# Connectors.net
KiCad netlist of a schematic drawn in Altium Designer
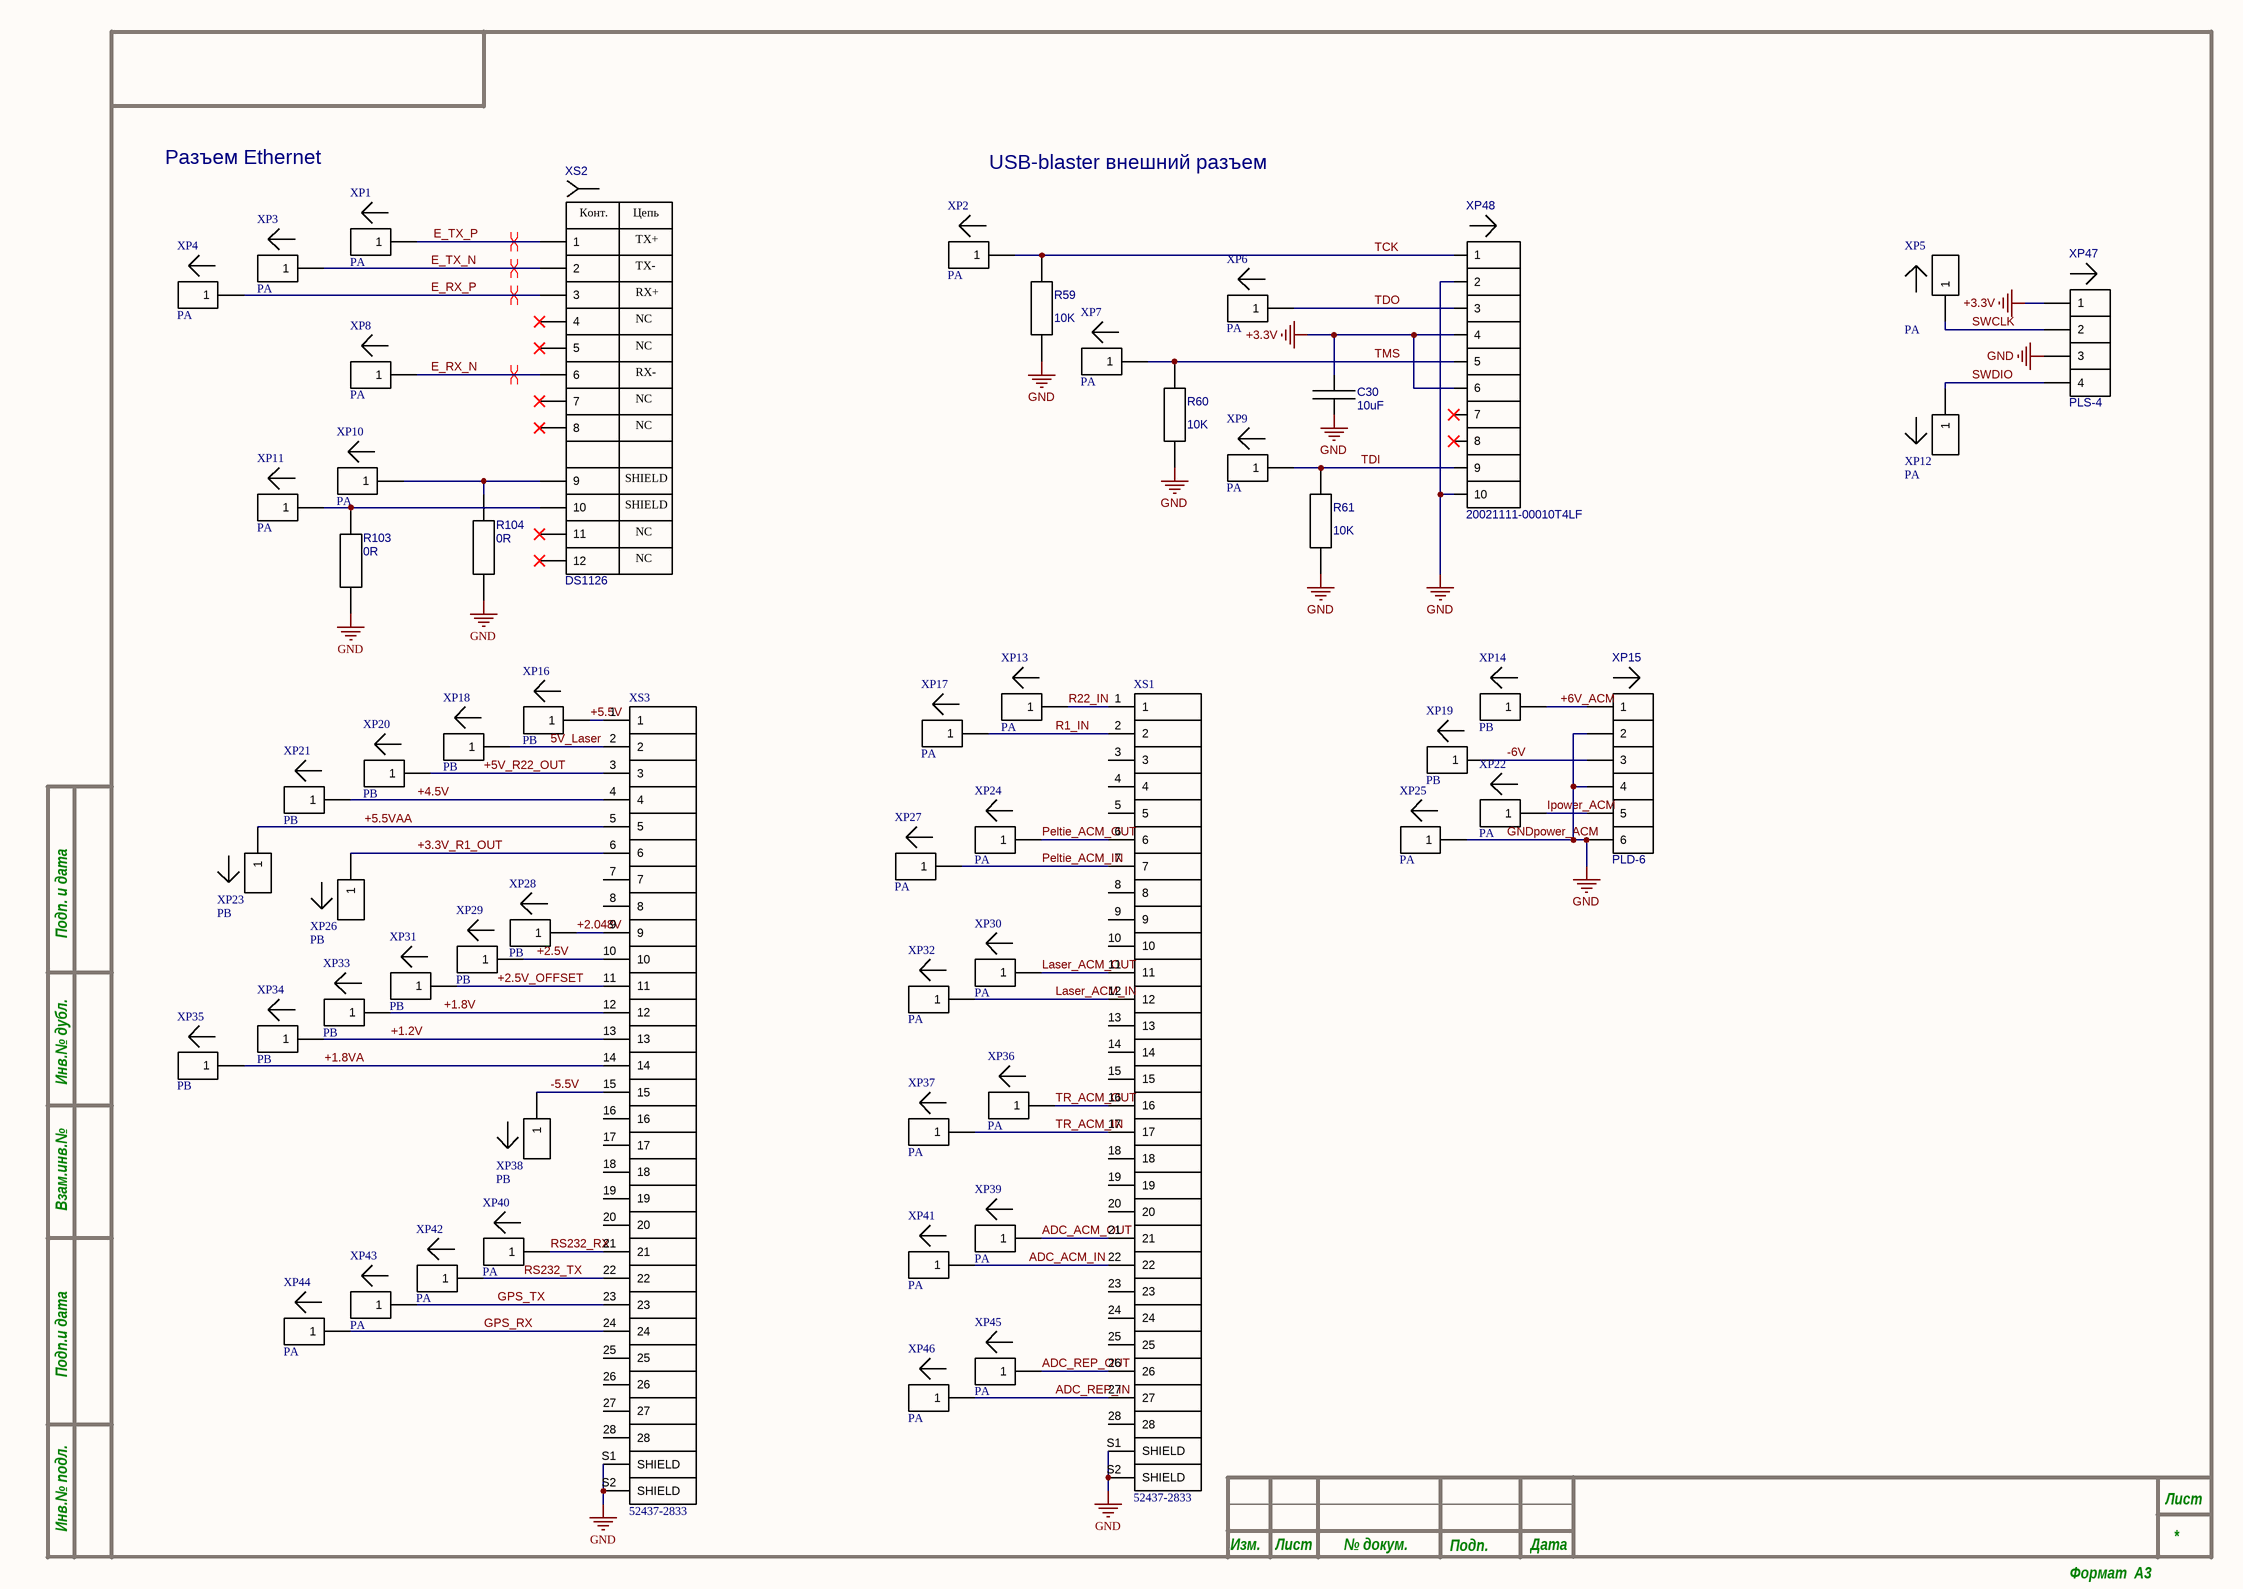
[diagram p0: Connectors — копия.SchDoc]

(export (version "E")
  (design (tool "Eeschema 10.0.6"))
  (components
    (comp (ref "C30")
      (value "10uF")
      (footprint "0402C")
      (description "C0402-10UF 10% 10V")
      (fields
        (field (name "PART NUMBER") "SMD CAP CER 10UF ±10% 10V X5R 0402")
        (field (name "ADDED_BY") "Rutel@Mail.ru")
      )
      (libsource (lib "Test_Stand_Pergam") (part "C0402-10UF 10% 10V"))
    )
    (comp (ref "R59")
      (value "10K")
      (footprint "R0402")
      (description "Resistor SMD 10K 1% 0402")
      (fields
        (field (name "PART NUMBER") "SMD RES 10 KOHM 1% ±100ppm/°C 0402")
        (field (name "ADDED_BY") "Rutel@teslatec.ru")
      )
      (libsource (lib "Test_Stand_Pergam") (part "R0402-10K"))
    )
    (comp (ref "R60")
      (value "10K")
      (footprint "R0402")
      (description "Resistor SMD 10K 1% 0402")
      (fields
        (field (name "PART NUMBER") "SMD RES 10 KOHM 1% ±100ppm/°C 0402")
        (field (name "ADDED_BY") "Rutel@teslatec.ru")
      )
      (libsource (lib "Test_Stand_Pergam") (part "R0402-10K"))
    )
    (comp (ref "R61")
      (value "10K")
      (footprint "R0402")
      (description "Resistor SMD 10K 1% 0402")
      (fields
        (field (name "PART NUMBER") "SMD RES 10 KOHM 1% ±100ppm/°C 0402")
        (field (name "ADDED_BY") "Rutel@teslatec.ru")
      )
      (libsource (lib "Test_Stand_Pergam") (part "R0402-10K"))
    )
    (comp (ref "R103")
      (value "0R")
      (footprint "R0402")
      (description "Resistor SMD 0R 1% 0402")
      (fields
        (field (name "PART NUMBER") "SMD RES 0R 0402")
        (field (name "ADDED_BY") "irdolgopolowa@yandex.ru")
      )
      (libsource (lib "Test_Stand_Pergam") (part "R0402-0R"))
    )
    (comp (ref "R104")
      (value "0R")
      (footprint "R0402")
      (description "Resistor SMD 0R 1% 0402")
      (fields
        (field (name "PART NUMBER") "SMD RES 0R 0402")
        (field (name "ADDED_BY") "irdolgopolowa@yandex.ru")
      )
      (libsource (lib "Test_Stand_Pergam") (part "R0402-0R"))
    )
    (comp (ref "XP1")
      (value "PA")
      (footprint "POGO PIN P100-A2/B1")
      (description "Pogo pin, 33.35x1.36")
      (fields
        (field (name "PART NUMBER") "P100-A2 / P100-A")
        (field (name "ADDED_BY") "irdolgopolowa@yandex.ru")
      )
      (libsource (lib "Test_Stand_Pergam") (part "P100-A2 / P100-A"))
    )
    (comp (ref "XP2")
      (value "PA")
      (footprint "POGO PIN P100-A2/B1")
      (description "Pogo pin, 33.35x1.36")
      (fields
        (field (name "PART NUMBER") "P100-A2 / P100-A")
        (field (name "ADDED_BY") "irdolgopolowa@yandex.ru")
      )
      (libsource (lib "Test_Stand_Pergam") (part "P100-A2 / P100-A"))
    )
    (comp (ref "XP3")
      (value "PA")
      (footprint "POGO PIN P100-A2/B1")
      (description "Pogo pin, 33.35x1.36")
      (fields
        (field (name "PART NUMBER") "P100-A2 / P100-A")
        (field (name "ADDED_BY") "irdolgopolowa@yandex.ru")
      )
      (libsource (lib "Test_Stand_Pergam") (part "P100-A2 / P100-A"))
    )
    (comp (ref "XP4")
      (value "PA")
      (footprint "POGO PIN P100-A2/B1")
      (description "Pogo pin, 33.35x1.36")
      (fields
        (field (name "PART NUMBER") "P100-A2 / P100-A")
        (field (name "ADDED_BY") "irdolgopolowa@yandex.ru")
      )
      (libsource (lib "Test_Stand_Pergam") (part "P100-A2 / P100-A"))
    )
    (comp (ref "XP5")
      (value "PA")
      (footprint "POGO PIN P100-A2/B1")
      (description "Pogo pin, 33.35x1.36")
      (fields
        (field (name "PART NUMBER") "P100-A2 / P100-A")
        (field (name "ADDED_BY") "irdolgopolowa@yandex.ru")
      )
      (libsource (lib "Test_Stand_Pergam") (part "P100-A2 / P100-A"))
    )
    (comp (ref "XP6")
      (value "PA")
      (footprint "POGO PIN P100-A2/B1")
      (description "Pogo pin, 33.35x1.36")
      (fields
        (field (name "PART NUMBER") "P100-A2 / P100-A")
        (field (name "ADDED_BY") "irdolgopolowa@yandex.ru")
      )
      (libsource (lib "Test_Stand_Pergam") (part "P100-A2 / P100-A"))
    )
    (comp (ref "XP7")
      (value "PA")
      (footprint "POGO PIN P100-A2/B1")
      (description "Pogo pin, 33.35x1.36")
      (fields
        (field (name "PART NUMBER") "P100-A2 / P100-A")
        (field (name "ADDED_BY") "irdolgopolowa@yandex.ru")
      )
      (libsource (lib "Test_Stand_Pergam") (part "P100-A2 / P100-A"))
    )
    (comp (ref "XP8")
      (value "PA")
      (footprint "POGO PIN P100-A2/B1")
      (description "Pogo pin, 33.35x1.36")
      (fields
        (field (name "PART NUMBER") "P100-A2 / P100-A")
        (field (name "ADDED_BY") "irdolgopolowa@yandex.ru")
      )
      (libsource (lib "Test_Stand_Pergam") (part "P100-A2 / P100-A"))
    )
    (comp (ref "XP9")
      (value "PA")
      (footprint "POGO PIN P100-A2/B1")
      (description "Pogo pin, 33.35x1.36")
      (fields
        (field (name "PART NUMBER") "P100-A2 / P100-A")
        (field (name "ADDED_BY") "irdolgopolowa@yandex.ru")
      )
      (libsource (lib "Test_Stand_Pergam") (part "P100-A2 / P100-A"))
    )
    (comp (ref "XP10")
      (value "PA")
      (footprint "POGO PIN P100-A2/B1")
      (description "Pogo pin, 33.35x1.36")
      (fields
        (field (name "PART NUMBER") "P100-A2 / P100-A")
        (field (name "ADDED_BY") "irdolgopolowa@yandex.ru")
      )
      (libsource (lib "Test_Stand_Pergam") (part "P100-A2 / P100-A"))
    )
    (comp (ref "XP11")
      (value "PA")
      (footprint "POGO PIN P100-A2/B1")
      (description "Pogo pin, 33.35x1.36")
      (fields
        (field (name "PART NUMBER") "P100-A2 / P100-A")
        (field (name "ADDED_BY") "irdolgopolowa@yandex.ru")
      )
      (libsource (lib "Test_Stand_Pergam") (part "P100-A2 / P100-A"))
    )
    (comp (ref "XP12")
      (value "PA")
      (footprint "POGO PIN P100-A2/B1")
      (description "Pogo pin, 33.35x1.36")
      (fields
        (field (name "PART NUMBER") "P100-A2 / P100-A")
        (field (name "ADDED_BY") "irdolgopolowa@yandex.ru")
      )
      (libsource (lib "Test_Stand_Pergam") (part "P100-A2 / P100-A"))
    )
    (comp (ref "XP13")
      (value "PA")
      (footprint "POGO PIN P100-A2/B1")
      (description "Pogo pin, 33.35x1.36")
      (fields
        (field (name "PART NUMBER") "P100-A2 / P100-A")
        (field (name "ADDED_BY") "irdolgopolowa@yandex.ru")
      )
      (libsource (lib "Test_Stand_Pergam") (part "P100-A2 / P100-A"))
    )
    (comp (ref "XP14")
      (value "PB")
      (footprint "POGO PIN P100-A2/B1")
      (description "Pogo pin, 33.35x1.36")
      (fields (field (name "PART NUMBER") "P100-B1") (field (name "ADDED_BY") "irdolgopolowa@yandex.ru"))
      (libsource (lib "Test_Stand_Pergam") (part "P100-B1"))
    )
    (comp (ref "XP15")
      (value "PLD-6")
      (footprint "PLD-6")
      (description "Pin Header Pitch 2.54mm")
      (fields
        (field (name "PART NUMBER") "PLD-6 (DS1021-2x3)")
        (field (name "ADDED_BY") "ponomarev_ke@teslatec.ru")
      )
      (libsource (lib "Test_Stand_Pergam") (part "PLD-6"))
    )
    (comp (ref "XP16")
      (value "PB")
      (footprint "POGO PIN P100-A2/B1")
      (description "Pogo pin, 33.35x1.36")
      (fields (field (name "PART NUMBER") "P100-B1") (field (name "ADDED_BY") "irdolgopolowa@yandex.ru"))
      (libsource (lib "Test_Stand_Pergam") (part "P100-B1"))
    )
    (comp (ref "XP17")
      (value "PA")
      (footprint "POGO PIN P100-A2/B1")
      (description "Pogo pin, 33.35x1.36")
      (fields
        (field (name "PART NUMBER") "P100-A2 / P100-A")
        (field (name "ADDED_BY") "irdolgopolowa@yandex.ru")
      )
      (libsource (lib "Test_Stand_Pergam") (part "P100-A2 / P100-A"))
    )
    (comp (ref "XP18")
      (value "PB")
      (footprint "POGO PIN P100-A2/B1")
      (description "Pogo pin, 33.35x1.36")
      (fields (field (name "PART NUMBER") "P100-B1") (field (name "ADDED_BY") "irdolgopolowa@yandex.ru"))
      (libsource (lib "Test_Stand_Pergam") (part "P100-B1"))
    )
    (comp (ref "XP19")
      (value "PB")
      (footprint "POGO PIN P100-A2/B1")
      (description "Pogo pin, 33.35x1.36")
      (fields (field (name "PART NUMBER") "P100-B1") (field (name "ADDED_BY") "irdolgopolowa@yandex.ru"))
      (libsource (lib "Test_Stand_Pergam") (part "P100-B1"))
    )
    (comp (ref "XP20")
      (value "PB")
      (footprint "POGO PIN P100-A2/B1")
      (description "Pogo pin, 33.35x1.36")
      (fields (field (name "PART NUMBER") "P100-B1") (field (name "ADDED_BY") "irdolgopolowa@yandex.ru"))
      (libsource (lib "Test_Stand_Pergam") (part "P100-B1"))
    )
    (comp (ref "XP21")
      (value "PB")
      (footprint "POGO PIN P100-A2/B1")
      (description "Pogo pin, 33.35x1.36")
      (fields (field (name "PART NUMBER") "P100-B1") (field (name "ADDED_BY") "irdolgopolowa@yandex.ru"))
      (libsource (lib "Test_Stand_Pergam") (part "P100-B1"))
    )
    (comp (ref "XP22")
      (value "PA")
      (footprint "POGO PIN P100-A2/B1")
      (description "Pogo pin, 33.35x1.36")
      (fields
        (field (name "PART NUMBER") "P100-A2 / P100-A")
        (field (name "ADDED_BY") "irdolgopolowa@yandex.ru")
      )
      (libsource (lib "Test_Stand_Pergam") (part "P100-A2 / P100-A"))
    )
    (comp (ref "XP23")
      (value "PB")
      (footprint "POGO PIN P100-A2/B1")
      (description "Pogo pin, 33.35x1.36")
      (fields (field (name "PART NUMBER") "P100-B1") (field (name "ADDED_BY") "irdolgopolowa@yandex.ru"))
      (libsource (lib "Test_Stand_Pergam") (part "P100-B1"))
    )
    (comp (ref "XP24")
      (value "PA")
      (footprint "POGO PIN P100-A2/B1")
      (description "Pogo pin, 33.35x1.36")
      (fields
        (field (name "PART NUMBER") "P100-A2 / P100-A")
        (field (name "ADDED_BY") "irdolgopolowa@yandex.ru")
      )
      (libsource (lib "Test_Stand_Pergam") (part "P100-A2 / P100-A"))
    )
    (comp (ref "XP25")
      (value "PA")
      (footprint "POGO PIN P100-A2/B1")
      (description "Pogo pin, 33.35x1.36")
      (fields
        (field (name "PART NUMBER") "P100-A2 / P100-A")
        (field (name "ADDED_BY") "irdolgopolowa@yandex.ru")
      )
      (libsource (lib "Test_Stand_Pergam") (part "P100-A2 / P100-A"))
    )
    (comp (ref "XP26")
      (value "PB")
      (footprint "POGO PIN P100-A2/B1")
      (description "Pogo pin, 33.35x1.36")
      (fields (field (name "PART NUMBER") "P100-B1") (field (name "ADDED_BY") "irdolgopolowa@yandex.ru"))
      (libsource (lib "Test_Stand_Pergam") (part "P100-B1"))
    )
    (comp (ref "XP27")
      (value "PA")
      (footprint "POGO PIN P100-A2/B1")
      (description "Pogo pin, 33.35x1.36")
      (fields
        (field (name "PART NUMBER") "P100-A2 / P100-A")
        (field (name "ADDED_BY") "irdolgopolowa@yandex.ru")
      )
      (libsource (lib "Test_Stand_Pergam") (part "P100-A2 / P100-A"))
    )
    (comp (ref "XP28")
      (value "PB")
      (footprint "POGO PIN P100-A2/B1")
      (description "Pogo pin, 33.35x1.36")
      (fields (field (name "PART NUMBER") "P100-B1") (field (name "ADDED_BY") "irdolgopolowa@yandex.ru"))
      (libsource (lib "Test_Stand_Pergam") (part "P100-B1"))
    )
    (comp (ref "XP29")
      (value "PB")
      (footprint "POGO PIN P100-A2/B1")
      (description "Pogo pin, 33.35x1.36")
      (fields (field (name "PART NUMBER") "P100-B1") (field (name "ADDED_BY") "irdolgopolowa@yandex.ru"))
      (libsource (lib "Test_Stand_Pergam") (part "P100-B1"))
    )
    (comp (ref "XP30")
      (value "PA")
      (footprint "POGO PIN P100-A2/B1")
      (description "Pogo pin, 33.35x1.36")
      (fields
        (field (name "PART NUMBER") "P100-A2 / P100-A")
        (field (name "ADDED_BY") "irdolgopolowa@yandex.ru")
      )
      (libsource (lib "Test_Stand_Pergam") (part "P100-A2 / P100-A"))
    )
    (comp (ref "XP31")
      (value "PB")
      (footprint "POGO PIN P100-A2/B1")
      (description "Pogo pin, 33.35x1.36")
      (fields (field (name "PART NUMBER") "P100-B1") (field (name "ADDED_BY") "irdolgopolowa@yandex.ru"))
      (libsource (lib "Test_Stand_Pergam") (part "P100-B1"))
    )
    (comp (ref "XP32")
      (value "PA")
      (footprint "POGO PIN P100-A2/B1")
      (description "Pogo pin, 33.35x1.36")
      (fields
        (field (name "PART NUMBER") "P100-A2 / P100-A")
        (field (name "ADDED_BY") "irdolgopolowa@yandex.ru")
      )
      (libsource (lib "Test_Stand_Pergam") (part "P100-A2 / P100-A"))
    )
    (comp (ref "XP33")
      (value "PB")
      (footprint "POGO PIN P100-A2/B1")
      (description "Pogo pin, 33.35x1.36")
      (fields (field (name "PART NUMBER") "P100-B1") (field (name "ADDED_BY") "irdolgopolowa@yandex.ru"))
      (libsource (lib "Test_Stand_Pergam") (part "P100-B1"))
    )
    (comp (ref "XP34")
      (value "PB")
      (footprint "POGO PIN P100-A2/B1")
      (description "Pogo pin, 33.35x1.36")
      (fields (field (name "PART NUMBER") "P100-B1") (field (name "ADDED_BY") "irdolgopolowa@yandex.ru"))
      (libsource (lib "Test_Stand_Pergam") (part "P100-B1"))
    )
    (comp (ref "XP35")
      (value "PB")
      (footprint "POGO PIN P100-A2/B1")
      (description "Pogo pin, 33.35x1.36")
      (fields (field (name "PART NUMBER") "P100-B1") (field (name "ADDED_BY") "irdolgopolowa@yandex.ru"))
      (libsource (lib "Test_Stand_Pergam") (part "P100-B1"))
    )
    (comp (ref "XP36")
      (value "PA")
      (footprint "POGO PIN P100-A2/B1")
      (description "Pogo pin, 33.35x1.36")
      (fields
        (field (name "PART NUMBER") "P100-A2 / P100-A")
        (field (name "ADDED_BY") "irdolgopolowa@yandex.ru")
      )
      (libsource (lib "Test_Stand_Pergam") (part "P100-A2 / P100-A"))
    )
    (comp (ref "XP37")
      (value "PA")
      (footprint "POGO PIN P100-A2/B1")
      (description "Pogo pin, 33.35x1.36")
      (fields
        (field (name "PART NUMBER") "P100-A2 / P100-A")
        (field (name "ADDED_BY") "irdolgopolowa@yandex.ru")
      )
      (libsource (lib "Test_Stand_Pergam") (part "P100-A2 / P100-A"))
    )
    (comp (ref "XP38")
      (value "PB")
      (footprint "POGO PIN P100-A2/B1")
      (description "Pogo pin, 33.35x1.36")
      (fields (field (name "PART NUMBER") "P100-B1") (field (name "ADDED_BY") "irdolgopolowa@yandex.ru"))
      (libsource (lib "Test_Stand_Pergam") (part "P100-B1"))
    )
    (comp (ref "XP39")
      (value "PA")
      (footprint "POGO PIN P100-A2/B1")
      (description "Pogo pin, 33.35x1.36")
      (fields
        (field (name "PART NUMBER") "P100-A2 / P100-A")
        (field (name "ADDED_BY") "irdolgopolowa@yandex.ru")
      )
      (libsource (lib "Test_Stand_Pergam") (part "P100-A2 / P100-A"))
    )
    (comp (ref "XP40")
      (value "PA")
      (footprint "POGO PIN P100-A2/B1")
      (description "Pogo pin, 33.35x1.36")
      (fields
        (field (name "PART NUMBER") "P100-A2 / P100-A")
        (field (name "ADDED_BY") "irdolgopolowa@yandex.ru")
      )
      (libsource (lib "Test_Stand_Pergam") (part "P100-A2 / P100-A"))
    )
    (comp (ref "XP41")
      (value "PA")
      (footprint "POGO PIN P100-A2/B1")
      (description "Pogo pin, 33.35x1.36")
      (fields
        (field (name "PART NUMBER") "P100-A2 / P100-A")
        (field (name "ADDED_BY") "irdolgopolowa@yandex.ru")
      )
      (libsource (lib "Test_Stand_Pergam") (part "P100-A2 / P100-A"))
    )
    (comp (ref "XP42")
      (value "PA")
      (footprint "POGO PIN P100-A2/B1")
      (description "Pogo pin, 33.35x1.36")
      (fields
        (field (name "PART NUMBER") "P100-A2 / P100-A")
        (field (name "ADDED_BY") "irdolgopolowa@yandex.ru")
      )
      (libsource (lib "Test_Stand_Pergam") (part "P100-A2 / P100-A"))
    )
    (comp (ref "XP43")
      (value "PA")
      (footprint "POGO PIN P100-A2/B1")
      (description "Pogo pin, 33.35x1.36")
      (fields
        (field (name "PART NUMBER") "P100-A2 / P100-A")
        (field (name "ADDED_BY") "irdolgopolowa@yandex.ru")
      )
      (libsource (lib "Test_Stand_Pergam") (part "P100-A2 / P100-A"))
    )
    (comp (ref "XP44")
      (value "PA")
      (footprint "POGO PIN P100-A2/B1")
      (description "Pogo pin, 33.35x1.36")
      (fields
        (field (name "PART NUMBER") "P100-A2 / P100-A")
        (field (name "ADDED_BY") "irdolgopolowa@yandex.ru")
      )
      (libsource (lib "Test_Stand_Pergam") (part "P100-A2 / P100-A"))
    )
    (comp (ref "XP45")
      (value "PA")
      (footprint "POGO PIN P100-A2/B1")
      (description "Pogo pin, 33.35x1.36")
      (fields
        (field (name "PART NUMBER") "P100-A2 / P100-A")
        (field (name "ADDED_BY") "irdolgopolowa@yandex.ru")
      )
      (libsource (lib "Test_Stand_Pergam") (part "P100-A2 / P100-A"))
    )
    (comp (ref "XP46")
      (value "PA")
      (footprint "POGO PIN P100-A2/B1")
      (description "Pogo pin, 33.35x1.36")
      (fields
        (field (name "PART NUMBER") "P100-A2 / P100-A")
        (field (name "ADDED_BY") "irdolgopolowa@yandex.ru")
      )
      (libsource (lib "Test_Stand_Pergam") (part "P100-A2 / P100-A"))
    )
    (comp (ref "XP47")
      (value "PLS-4")
      (footprint "PLS-4")
      (description "HEADER 2.54mm")
      (fields (field (name "MATING PART") "BLS-4") (field (name "ADDED_BY") "irdolgopolowa@yandex.ru"))
      (libsource (lib "Test_Stand_Pergam") (part "PLS-4"))
    )
    (comp (ref "XP48")
      (value "20021111-00010T4LF")
      (footprint "20021111-00010T4LF")
      (description "20021111-00010T4LF. pin 10")
      (fields (field (name "ADDED_BY") "irdolgopolowa@yandex.ru"))
      (libsource (lib "Test_Stand_Pergam") (part "20021111-00010T4LF"))
    )
    (comp (ref "XS1")
      (value "52437-2833")
      (footprint "MOLEX_52437-2833")
      (description "28 Position FFC, FPC Connector Contacts, Bottom 0.020 _0.50mm_ Surface Mount, Right Angle")
      (fields
        (field (name "PART NUMBER") "52437-2833 (MOLEX)")
        (field (name "MATING PART") "FFCA 28pin, 0.5mm pitch, AVM 20624 80C 60V VW-1")
        (field (name "ADDED_BY") "ridel_av@teslatec.ru")
      )
      (libsource (lib "Test_Stand_Pergam") (part "52437-2833"))
    )
    (comp (ref "XS2")
      (value "DS1126")
      (footprint "DS1126")
      (description "Ethernet PCB 8/8 RJ45")
      (fields (field (name "ADDED_BY") "irdolgopolowa@yandex.ru"))
      (libsource (lib "Test_Stand_Pergam") (part "DS1126"))
    )
    (comp (ref "XS3")
      (value "52437-2833")
      (footprint "MOLEX_52437-2833")
      (description "28 Position FFC, FPC Connector Contacts, Bottom 0.020 _0.50mm_ Surface Mount, Right Angle")
      (fields
        (field (name "PART NUMBER") "52437-2833 (MOLEX)")
        (field (name "MATING PART") "FFCA 28pin, 0.5mm pitch, AVM 20624 80C 60V VW-1")
        (field (name "ADDED_BY") "ridel_av@teslatec.ru")
      )
      (libsource (lib "Test_Stand_Pergam") (part "52437-2833"))
    )
  )
  (nets
    (net (code "1") (name "+3.3V") (class "Default")
      (node (ref "C30") (pin "2") (pinfunction "2_2") (pintype "passive"))
      (node (ref "XP47") (pin "1") (pinfunction "1_1") (pintype "passive"))
      (node (ref "XP48") (pin "4") (pinfunction "4_4") (pintype "passive"))
      (node (ref "XP48") (pin "6") (pinfunction "6_6") (pintype "passive"))
    )
    (net (code "2") (name "/+1.2V") (class "Default")
      (node (ref "XP34") (pin "1") (pinfunction "1_1") (pintype "passive"))
      (node (ref "XS3") (pin "13") (pinfunction "13_13") (pintype "passive"))
    )
    (net (code "3") (name "/+1.8V") (class "Default")
      (node (ref "XP33") (pin "1") (pinfunction "1_1") (pintype "passive"))
      (node (ref "XS3") (pin "12") (pinfunction "12_12") (pintype "passive"))
    )
    (net (code "4") (name "/+1.8VA") (class "Default")
      (node (ref "XP35") (pin "1") (pinfunction "1_1") (pintype "passive"))
      (node (ref "XS3") (pin "14") (pinfunction "14_14") (pintype "passive"))
    )
    (net (code "5") (name "/+2.5V") (class "Default")
      (node (ref "XP29") (pin "1") (pinfunction "1_1") (pintype "passive"))
      (node (ref "XS3") (pin "10") (pinfunction "10_10") (pintype "passive"))
    )
    (net (code "6") (name "/+2.5V_OFFSET") (class "Default")
      (node (ref "XP31") (pin "1") (pinfunction "1_1") (pintype "passive"))
      (node (ref "XS3") (pin "11") (pinfunction "11_11") (pintype "passive"))
    )
    (net (code "7") (name "/+2.048V") (class "Default")
      (node (ref "XP28") (pin "1") (pinfunction "1_1") (pintype "passive"))
      (node (ref "XS3") (pin "9") (pinfunction "9_9") (pintype "passive"))
    )
    (net (code "8") (name "/+3.3V_R1_OUT") (class "Default")
      (node (ref "XP26") (pin "1") (pinfunction "1_1") (pintype "passive"))
      (node (ref "XS3") (pin "6") (pinfunction "6_6") (pintype "passive"))
    )
    (net (code "9") (name "/+4.5V") (class "Default")
      (node (ref "XP21") (pin "1") (pinfunction "1_1") (pintype "passive"))
      (node (ref "XS3") (pin "4") (pinfunction "4_4") (pintype "passive"))
    )
    (net (code "10") (name "/+5.5V") (class "Default")
      (node (ref "XP16") (pin "1") (pinfunction "1_1") (pintype "passive"))
      (node (ref "XS3") (pin "1") (pinfunction "1_1") (pintype "passive"))
    )
    (net (code "11") (name "/+5.5VAA") (class "Default")
      (node (ref "XP23") (pin "1") (pinfunction "1_1") (pintype "passive"))
      (node (ref "XS3") (pin "5") (pinfunction "5_5") (pintype "passive"))
    )
    (net (code "12") (name "/+5V_R22_OUT") (class "Default")
      (node (ref "XP20") (pin "1") (pinfunction "1_1") (pintype "passive"))
      (node (ref "XS3") (pin "3") (pinfunction "3_3") (pintype "passive"))
    )
    (net (code "13") (name "/+6V_ACM") (class "Default")
      (node (ref "XP14") (pin "1") (pinfunction "1_1") (pintype "passive"))
      (node (ref "XP15") (pin "1") (pinfunction "1_1") (pintype "passive"))
    )
    (net (code "14") (name "/-5.5V") (class "Default")
      (node (ref "XP38") (pin "1") (pinfunction "1_1") (pintype "passive"))
      (node (ref "XS3") (pin "15") (pinfunction "15_15") (pintype "passive"))
    )
    (net (code "15") (name "/-6V") (class "Default")
      (node (ref "XP15") (pin "3") (pinfunction "3_3") (pintype "passive"))
      (node (ref "XP19") (pin "1") (pinfunction "1_1") (pintype "passive"))
    )
    (net (code "16") (name "/5V_Laser") (class "Default")
      (node (ref "XP18") (pin "1") (pinfunction "1_1") (pintype "passive"))
      (node (ref "XS3") (pin "2") (pinfunction "2_2") (pintype "passive"))
    )
    (net (code "17") (name "/ADC_ACM_IN") (class "Default")
      (node (ref "XP41") (pin "1") (pinfunction "1_1") (pintype "passive"))
      (node (ref "XS1") (pin "22") (pinfunction "22_22") (pintype "passive"))
    )
    (net (code "18") (name "/ADC_ACM_OUT") (class "Default")
      (node (ref "XP39") (pin "1") (pinfunction "1_1") (pintype "passive"))
      (node (ref "XS1") (pin "21") (pinfunction "21_21") (pintype "passive"))
    )
    (net (code "19") (name "/ADC_REP_IN") (class "Default")
      (node (ref "XP46") (pin "1") (pinfunction "1_1") (pintype "passive"))
      (node (ref "XS1") (pin "27") (pinfunction "27_27") (pintype "passive"))
    )
    (net (code "20") (name "/ADC_REP_OUT") (class "Default")
      (node (ref "XP45") (pin "1") (pinfunction "1_1") (pintype "passive"))
      (node (ref "XS1") (pin "26") (pinfunction "26_26") (pintype "passive"))
    )
    (net (code "21") (name "/E_RX_N") (class "Default")
      (node (ref "XP8") (pin "1") (pinfunction "1_1") (pintype "passive"))
      (node (ref "XS2") (pin "6") (pinfunction "6_6") (pintype "passive"))
    )
    (net (code "22") (name "/E_RX_P") (class "Default")
      (node (ref "XP4") (pin "1") (pinfunction "1_1") (pintype "passive"))
      (node (ref "XS2") (pin "3") (pinfunction "3_3") (pintype "passive"))
    )
    (net (code "23") (name "/E_TX_N") (class "Default")
      (node (ref "XP3") (pin "1") (pinfunction "1_1") (pintype "passive"))
      (node (ref "XS2") (pin "2") (pinfunction "2_2") (pintype "passive"))
    )
    (net (code "24") (name "/E_TX_P") (class "Default")
      (node (ref "XP1") (pin "1") (pinfunction "1_1") (pintype "passive"))
      (node (ref "XS2") (pin "1") (pinfunction "1_1") (pintype "passive"))
    )
    (net (code "25") (name "/GPS_RX") (class "Default")
      (node (ref "XP44") (pin "1") (pinfunction "1_1") (pintype "passive"))
      (node (ref "XS3") (pin "24") (pinfunction "24_24") (pintype "passive"))
    )
    (net (code "26") (name "/GPS_TX") (class "Default")
      (node (ref "XP43") (pin "1") (pinfunction "1_1") (pintype "passive"))
      (node (ref "XS3") (pin "23") (pinfunction "23_23") (pintype "passive"))
    )
    (net (code "27") (name "/Ipower_ACM") (class "Default")
      (node (ref "XP15") (pin "5") (pinfunction "5_5") (pintype "passive"))
      (node (ref "XP22") (pin "1") (pinfunction "1_1") (pintype "passive"))
    )
    (net (code "28") (name "/Laser_ACM_IN") (class "Default")
      (node (ref "XP32") (pin "1") (pinfunction "1_1") (pintype "passive"))
      (node (ref "XS1") (pin "12") (pinfunction "12_12") (pintype "passive"))
    )
    (net (code "29") (name "/Laser_ACM_OUT") (class "Default")
      (node (ref "XP30") (pin "1") (pinfunction "1_1") (pintype "passive"))
      (node (ref "XS1") (pin "11") (pinfunction "11_11") (pintype "passive"))
    )
    (net (code "30") (name "/Peltie_ACM_IN") (class "Default")
      (node (ref "XP27") (pin "1") (pinfunction "1_1") (pintype "passive"))
      (node (ref "XS1") (pin "7") (pinfunction "7_7") (pintype "passive"))
    )
    (net (code "31") (name "/Peltie_ACM_OUT") (class "Default")
      (node (ref "XP24") (pin "1") (pinfunction "1_1") (pintype "passive"))
      (node (ref "XS1") (pin "6") (pinfunction "6_6") (pintype "passive"))
    )
    (net (code "32") (name "/R1_IN") (class "Default")
      (node (ref "XP17") (pin "1") (pinfunction "1_1") (pintype "passive"))
      (node (ref "XS1") (pin "2") (pinfunction "2_2") (pintype "passive"))
    )
    (net (code "33") (name "/R22_IN") (class "Default")
      (node (ref "XP13") (pin "1") (pinfunction "1_1") (pintype "passive"))
      (node (ref "XS1") (pin "1") (pinfunction "1_1") (pintype "passive"))
    )
    (net (code "34") (name "/RS232_RX") (class "Default")
      (node (ref "XP40") (pin "1") (pinfunction "1_1") (pintype "passive"))
      (node (ref "XS3") (pin "21") (pinfunction "21_21") (pintype "passive"))
    )
    (net (code "35") (name "/RS232_TX") (class "Default")
      (node (ref "XP42") (pin "1") (pinfunction "1_1") (pintype "passive"))
      (node (ref "XS3") (pin "22") (pinfunction "22_22") (pintype "passive"))
    )
    (net (code "36") (name "/SWCLK") (class "Default")
      (node (ref "XP47") (pin "2") (pinfunction "2_2") (pintype "passive"))
      (node (ref "XP5") (pin "1") (pinfunction "1_1") (pintype "passive"))
    )
    (net (code "37") (name "/SWDIO") (class "Default")
      (node (ref "XP12") (pin "1") (pinfunction "1_1") (pintype "passive"))
      (node (ref "XP47") (pin "4") (pinfunction "4_4") (pintype "passive"))
    )
    (net (code "38") (name "/TCK") (class "Default")
      (node (ref "R59") (pin "2") (pinfunction "2_2") (pintype "passive"))
      (node (ref "XP2") (pin "1") (pinfunction "1_1") (pintype "passive"))
      (node (ref "XP48") (pin "1") (pinfunction "1_1") (pintype "passive"))
    )
    (net (code "39") (name "/TDI") (class "Default")
      (node (ref "R61") (pin "2") (pinfunction "2_2") (pintype "passive"))
      (node (ref "XP48") (pin "9") (pinfunction "9_9") (pintype "passive"))
      (node (ref "XP9") (pin "1") (pinfunction "1_1") (pintype "passive"))
    )
    (net (code "40") (name "/TDO") (class "Default")
      (node (ref "XP48") (pin "3") (pinfunction "3_3") (pintype "passive"))
      (node (ref "XP6") (pin "1") (pinfunction "1_1") (pintype "passive"))
    )
    (net (code "41") (name "/TMS") (class "Default")
      (node (ref "R60") (pin "2") (pinfunction "2_2") (pintype "passive"))
      (node (ref "XP48") (pin "5") (pinfunction "5_5") (pintype "passive"))
      (node (ref "XP7") (pin "1") (pinfunction "1_1") (pintype "passive"))
    )
    (net (code "42") (name "/TR_ACM_IN") (class "Default")
      (node (ref "XP37") (pin "1") (pinfunction "1_1") (pintype "passive"))
      (node (ref "XS1") (pin "17") (pinfunction "17_17") (pintype "passive"))
    )
    (net (code "43") (name "/TR_ACM_OUT") (class "Default")
      (node (ref "XP36") (pin "1") (pinfunction "1_1") (pintype "passive"))
      (node (ref "XS1") (pin "16") (pinfunction "16_16") (pintype "passive"))
    )
    (net (code "44") (name "GND") (class "Default")
      (node (ref "C30") (pin "1") (pinfunction "1_1") (pintype "passive"))
      (node (ref "R103") (pin "1") (pinfunction "1_1") (pintype "passive"))
      (node (ref "R104") (pin "1") (pinfunction "1_1") (pintype "passive"))
      (node (ref "R59") (pin "1") (pinfunction "1_1") (pintype "passive"))
      (node (ref "R60") (pin "1") (pinfunction "1_1") (pintype "passive"))
      (node (ref "R61") (pin "1") (pinfunction "1_1") (pintype "passive"))
      (node (ref "XP15") (pin "2") (pinfunction "2_2") (pintype "passive"))
      (node (ref "XP15") (pin "4") (pinfunction "4_4") (pintype "passive"))
      (node (ref "XP15") (pin "6") (pinfunction "6_6") (pintype "passive"))
      (node (ref "XP25") (pin "1") (pinfunction "1_1") (pintype "passive"))
      (node (ref "XP47") (pin "3") (pinfunction "3_3") (pintype "passive"))
      (node (ref "XP48") (pin "10") (pinfunction "10_10") (pintype "passive"))
      (node (ref "XP48") (pin "2") (pinfunction "2_2") (pintype "passive"))
      (node (ref "XS1") (pin "S1") (pinfunction "SHIELD_S1") (pintype "passive"))
      (node (ref "XS1") (pin "S2") (pinfunction "SHIELD_S2") (pintype "passive"))
      (node (ref "XS3") (pin "S1") (pinfunction "SHIELD_S1") (pintype "passive"))
      (node (ref "XS3") (pin "S2") (pinfunction "SHIELD_S2") (pintype "passive"))
    )
    (net (code "45") (name "Net-(R103-Pad2)") (class "Default")
      (node (ref "R103") (pin "2") (pinfunction "2_2") (pintype "passive"))
      (node (ref "XP11") (pin "1") (pinfunction "1_1") (pintype "passive"))
      (node (ref "XS2") (pin "10") (pinfunction "10_10") (pintype "passive"))
    )
    (net (code "46") (name "Net-(R104-Pad2)") (class "Default")
      (node (ref "R104") (pin "2") (pinfunction "2_2") (pintype "passive"))
      (node (ref "XP10") (pin "1") (pinfunction "1_1") (pintype "passive"))
      (node (ref "XS2") (pin "9") (pinfunction "9_9") (pintype "passive"))
    )
    (net (code "47") (name "unconnected-(XP48-Pad7)") (class "Default")
      (node (ref "XP48") (pin "7") (pinfunction "7_7") (pintype "passive+no_connect"))
    )
    (net (code "48") (name "unconnected-(XP48-Pad8)") (class "Default")
      (node (ref "XP48") (pin "8") (pinfunction "8_8") (pintype "passive+no_connect"))
    )
    (net (code "49") (name "unconnected-(XS1-Pad3)") (class "Default")
      (node (ref "XS1") (pin "3") (pinfunction "3_3") (pintype "passive"))
    )
    (net (code "50") (name "unconnected-(XS1-Pad4)") (class "Default")
      (node (ref "XS1") (pin "4") (pinfunction "4_4") (pintype "passive"))
    )
    (net (code "51") (name "unconnected-(XS1-Pad5)") (class "Default")
      (node (ref "XS1") (pin "5") (pinfunction "5_5") (pintype "passive"))
    )
    (net (code "52") (name "unconnected-(XS1-Pad8)") (class "Default")
      (node (ref "XS1") (pin "8") (pinfunction "8_8") (pintype "passive"))
    )
    (net (code "53") (name "unconnected-(XS1-Pad9)") (class "Default")
      (node (ref "XS1") (pin "9") (pinfunction "9_9") (pintype "passive"))
    )
    (net (code "54") (name "unconnected-(XS1-Pad10)") (class "Default")
      (node (ref "XS1") (pin "10") (pinfunction "10_10") (pintype "passive"))
    )
    (net (code "55") (name "unconnected-(XS1-Pad13)") (class "Default")
      (node (ref "XS1") (pin "13") (pinfunction "13_13") (pintype "passive"))
    )
    (net (code "56") (name "unconnected-(XS1-Pad14)") (class "Default")
      (node (ref "XS1") (pin "14") (pinfunction "14_14") (pintype "passive"))
    )
    (net (code "57") (name "unconnected-(XS1-Pad15)") (class "Default")
      (node (ref "XS1") (pin "15") (pinfunction "15_15") (pintype "passive"))
    )
    (net (code "58") (name "unconnected-(XS1-Pad18)") (class "Default")
      (node (ref "XS1") (pin "18") (pinfunction "18_18") (pintype "passive"))
    )
    (net (code "59") (name "unconnected-(XS1-Pad19)") (class "Default")
      (node (ref "XS1") (pin "19") (pinfunction "19_19") (pintype "passive"))
    )
    (net (code "60") (name "unconnected-(XS1-Pad20)") (class "Default")
      (node (ref "XS1") (pin "20") (pinfunction "20_20") (pintype "passive"))
    )
    (net (code "61") (name "unconnected-(XS1-Pad23)") (class "Default")
      (node (ref "XS1") (pin "23") (pinfunction "23_23") (pintype "passive"))
    )
    (net (code "62") (name "unconnected-(XS1-Pad24)") (class "Default")
      (node (ref "XS1") (pin "24") (pinfunction "24_24") (pintype "passive"))
    )
    (net (code "63") (name "unconnected-(XS1-Pad25)") (class "Default")
      (node (ref "XS1") (pin "25") (pinfunction "25_25") (pintype "passive"))
    )
    (net (code "64") (name "unconnected-(XS1-Pad28)") (class "Default")
      (node (ref "XS1") (pin "28") (pinfunction "28_28") (pintype "passive"))
    )
    (net (code "65") (name "unconnected-(XS2-Pad4)") (class "Default")
      (node (ref "XS2") (pin "4") (pinfunction "4_4") (pintype "passive+no_connect"))
    )
    (net (code "66") (name "unconnected-(XS2-Pad5)") (class "Default")
      (node (ref "XS2") (pin "5") (pinfunction "5_5") (pintype "passive+no_connect"))
    )
    (net (code "67") (name "unconnected-(XS2-Pad7)") (class "Default")
      (node (ref "XS2") (pin "7") (pinfunction "7_7") (pintype "passive+no_connect"))
    )
    (net (code "68") (name "unconnected-(XS2-Pad8)") (class "Default")
      (node (ref "XS2") (pin "8") (pinfunction "8_8") (pintype "passive+no_connect"))
    )
    (net (code "69") (name "unconnected-(XS2-Pad11)") (class "Default")
      (node (ref "XS2") (pin "11") (pinfunction "11_11") (pintype "passive+no_connect"))
    )
    (net (code "70") (name "unconnected-(XS2-Pad12)") (class "Default")
      (node (ref "XS2") (pin "12") (pinfunction "12_12") (pintype "passive+no_connect"))
    )
    (net (code "71") (name "unconnected-(XS3-Pad7)") (class "Default")
      (node (ref "XS3") (pin "7") (pinfunction "7_7") (pintype "passive"))
    )
    (net (code "72") (name "unconnected-(XS3-Pad8)") (class "Default")
      (node (ref "XS3") (pin "8") (pinfunction "8_8") (pintype "passive"))
    )
    (net (code "73") (name "unconnected-(XS3-Pad16)") (class "Default")
      (node (ref "XS3") (pin "16") (pinfunction "16_16") (pintype "passive"))
    )
    (net (code "74") (name "unconnected-(XS3-Pad17)") (class "Default")
      (node (ref "XS3") (pin "17") (pinfunction "17_17") (pintype "passive"))
    )
    (net (code "75") (name "unconnected-(XS3-Pad18)") (class "Default")
      (node (ref "XS3") (pin "18") (pinfunction "18_18") (pintype "passive"))
    )
    (net (code "76") (name "unconnected-(XS3-Pad19)") (class "Default")
      (node (ref "XS3") (pin "19") (pinfunction "19_19") (pintype "passive"))
    )
    (net (code "77") (name "unconnected-(XS3-Pad20)") (class "Default")
      (node (ref "XS3") (pin "20") (pinfunction "20_20") (pintype "passive"))
    )
    (net (code "78") (name "unconnected-(XS3-Pad25)") (class "Default")
      (node (ref "XS3") (pin "25") (pinfunction "25_25") (pintype "passive"))
    )
    (net (code "79") (name "unconnected-(XS3-Pad26)") (class "Default")
      (node (ref "XS3") (pin "26") (pinfunction "26_26") (pintype "passive"))
    )
    (net (code "80") (name "unconnected-(XS3-Pad27)") (class "Default")
      (node (ref "XS3") (pin "27") (pinfunction "27_27") (pintype "passive"))
    )
    (net (code "81") (name "unconnected-(XS3-Pad28)") (class "Default")
      (node (ref "XS3") (pin "28") (pinfunction "28_28") (pintype "passive"))
    )
  )
)
